# 555_Timer.net
KiCad netlist of a schematic drawn in EAGLE
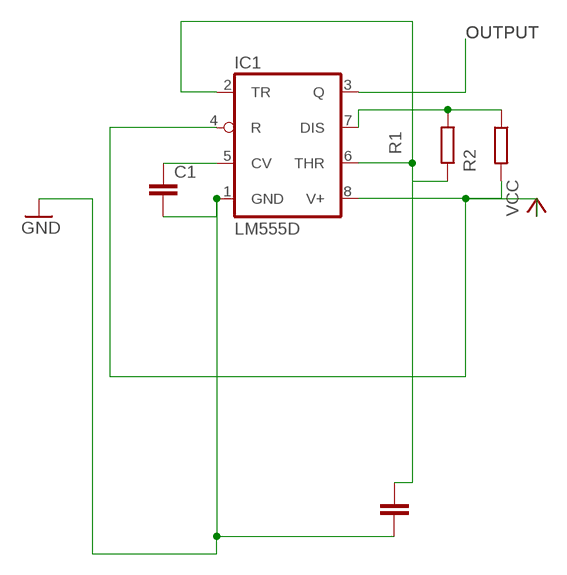
[diagram p0: schematic, sheet 1]

(export (version "E")
  (design (tool "Eeschema 10.0.6"))
  (components
    (comp (ref "C1")
      (value "C-EU025-024X044")
      (footprint "eagle-import:C025-024X044")
      (libsource (lib "eagle-import") (part "C-EU025-024X044"))
    )
    (comp (ref "C3")
      (value "C-EU025-024X044")
      (footprint "eagle-import:C025-024X044")
      (libsource (lib "eagle-import") (part "C-EU025-024X044"))
    )
    (comp (ref "IC1")
      (value "LM555D")
      (footprint "eagle-import:SO08")
      (libsource (lib "eagle-import") (part "555DLM"))
    )
    (comp (ref "R1")
      (value "R-EU_0204/5")
      (footprint "eagle-import:0204_5")
      (libsource (lib "eagle-import") (part "R-EU_0204/5"))
    )
    (comp (ref "R2")
      (value "R-EU_0204/5")
      (footprint "eagle-import:0204_5")
      (libsource (lib "eagle-import") (part "R-EU_0204/5"))
    )
  )
  (nets
    (net (code "1") (name "/OUTPUT") (class "Default")
      (node (ref "IC1") (pin "3") (pinfunction "Q_3") (pintype "output"))
    )
    (net (code "2") (name "GND") (class "Default")
      (node (ref "C1") (pin "2") (pinfunction "2_2") (pintype "passive"))
      (node (ref "C3") (pin "2") (pinfunction "2_2") (pintype "passive"))
      (node (ref "IC1") (pin "1") (pinfunction "GND_1") (pintype "power_in"))
    )
    (net (code "3") (name "Net-(IC1-CV)") (class "Default")
      (node (ref "C1") (pin "1") (pinfunction "1_1") (pintype "passive"))
      (node (ref "IC1") (pin "5") (pinfunction "CV_5") (pintype "input"))
    )
    (net (code "4") (name "Net-(IC1-DIS)") (class "Default")
      (node (ref "IC1") (pin "7") (pinfunction "DIS_7") (pintype "input"))
      (node (ref "R1") (pin "2") (pinfunction "2_2") (pintype "passive"))
      (node (ref "R2") (pin "1") (pinfunction "1_1") (pintype "passive"))
    )
    (net (code "5") (name "Net-(IC1-THR)") (class "Default")
      (node (ref "C3") (pin "1") (pinfunction "1_1") (pintype "passive"))
      (node (ref "IC1") (pin "2") (pinfunction "TR_2") (pintype "input"))
      (node (ref "IC1") (pin "6") (pinfunction "THR_6") (pintype "input"))
      (node (ref "R1") (pin "1") (pinfunction "1_1") (pintype "passive"))
    )
    (net (code "6") (name "VCC") (class "Default")
      (node (ref "IC1") (pin "4") (pinfunction "R_4") (pintype "input"))
      (node (ref "IC1") (pin "8") (pinfunction "V+_8") (pintype "power_in"))
      (node (ref "R2") (pin "2") (pinfunction "2_2") (pintype "passive"))
    )
  )
)
